# Khoi_Switch.net
KiCad netlist of a schematic drawn in Altium Designer
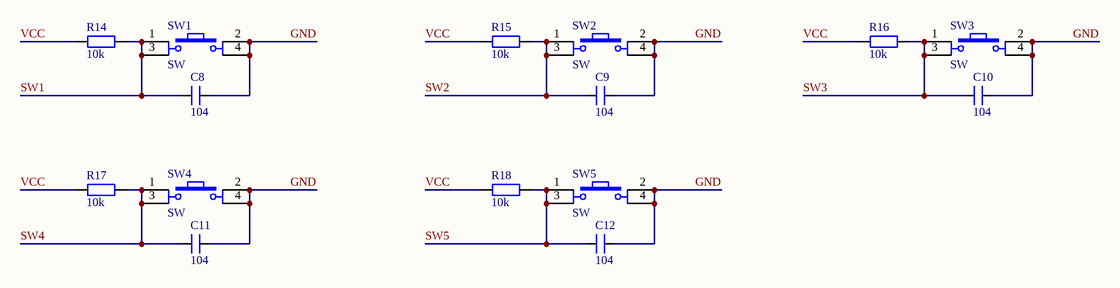
[diagram p0: Khoi_Switch.SchDoc]

(export (version "E")
  (design (tool "Eeschema 10.0.6"))
  (components
    (comp (ref "C8")
      (value "104")
      (footprint "CN2")
      (description "Cap np 104 => 105pF")
      (libsource (lib "My Library") (part "CN2"))
    )
    (comp (ref "C9")
      (value "104")
      (footprint "CN2")
      (description "Cap np 104 => 105pF")
      (libsource (lib "My Library") (part "CN2"))
    )
    (comp (ref "C10")
      (value "104")
      (footprint "CN2")
      (description "Cap np 104 => 105pF")
      (libsource (lib "My Library") (part "CN2"))
    )
    (comp (ref "C11")
      (value "104")
      (footprint "CN2")
      (description "Cap np 104 => 105pF")
      (libsource (lib "My Library") (part "CN2"))
    )
    (comp (ref "C12")
      (value "104")
      (footprint "CN2")
      (description "Cap np 104 => 105pF")
      (libsource (lib "My Library") (part "CN2"))
    )
    (comp (ref "R14")
      (value "10k")
      (footprint "R1/4W")
      (description "Resistor 1/4W")
      (libsource (lib "My Library") (part "R1/4W"))
    )
    (comp (ref "R15")
      (value "10k")
      (footprint "R1/4W")
      (description "Resistor 1/4W")
      (libsource (lib "My Library") (part "R1/4W"))
    )
    (comp (ref "R16")
      (value "10k")
      (footprint "R1/4W")
      (description "Resistor 1/4W")
      (libsource (lib "My Library") (part "R1/4W"))
    )
    (comp (ref "R17")
      (value "10k")
      (footprint "R1/4W")
      (description "Resistor 1/4W")
      (libsource (lib "My Library") (part "R1/4W"))
    )
    (comp (ref "R18")
      (value "10k")
      (footprint "R1/4W")
      (description "Resistor 1/4W")
      (libsource (lib "My Library") (part "R1/4W"))
    )
    (comp (ref "SW1")
      (value "SW")
      (footprint "SW4")
      (description "Switch button 4 pin")
      (libsource (lib "My Library") (part "SW4"))
    )
    (comp (ref "SW2")
      (value "SW")
      (footprint "SW4")
      (description "Switch button 4 pin")
      (libsource (lib "My Library") (part "SW4"))
    )
    (comp (ref "SW3")
      (value "SW")
      (footprint "SW4")
      (description "Switch button 4 pin")
      (libsource (lib "My Library") (part "SW4"))
    )
    (comp (ref "SW4")
      (value "SW")
      (footprint "SW4")
      (description "Switch button 4 pin")
      (libsource (lib "My Library") (part "SW4"))
    )
    (comp (ref "SW5")
      (value "SW")
      (footprint "SW4")
      (description "Switch button 4 pin")
      (libsource (lib "My Library") (part "SW4"))
    )
  )
  (nets
    (net (code "1") (name "/GND") (class "Default")
      (node (ref "C10") (pin "2") (pinfunction "2_2") (pintype "passive"))
      (node (ref "C11") (pin "2") (pinfunction "2_2") (pintype "passive"))
      (node (ref "C12") (pin "2") (pinfunction "2_2") (pintype "passive"))
      (node (ref "C8") (pin "2") (pinfunction "2_2") (pintype "passive"))
      (node (ref "C9") (pin "2") (pinfunction "2_2") (pintype "passive"))
      (node (ref "SW1") (pin "2") (pintype "passive"))
      (node (ref "SW1") (pin "4") (pintype "passive"))
      (node (ref "SW2") (pin "2") (pintype "passive"))
      (node (ref "SW2") (pin "4") (pintype "passive"))
      (node (ref "SW3") (pin "2") (pintype "passive"))
      (node (ref "SW3") (pin "4") (pintype "passive"))
      (node (ref "SW4") (pin "2") (pintype "passive"))
      (node (ref "SW4") (pin "4") (pintype "passive"))
      (node (ref "SW5") (pin "2") (pintype "passive"))
      (node (ref "SW5") (pin "4") (pintype "passive"))
    )
    (net (code "2") (name "/SW1") (class "Default")
      (node (ref "C8") (pin "1") (pinfunction "1_1") (pintype "passive"))
      (node (ref "R14") (pin "2") (pinfunction "2_2") (pintype "passive"))
      (node (ref "SW1") (pin "1") (pintype "passive"))
      (node (ref "SW1") (pin "3") (pintype "passive"))
    )
    (net (code "3") (name "/SW2") (class "Default")
      (node (ref "C9") (pin "1") (pinfunction "1_1") (pintype "passive"))
      (node (ref "R15") (pin "2") (pinfunction "2_2") (pintype "passive"))
      (node (ref "SW2") (pin "1") (pintype "passive"))
      (node (ref "SW2") (pin "3") (pintype "passive"))
    )
    (net (code "4") (name "/SW3") (class "Default")
      (node (ref "C10") (pin "1") (pinfunction "1_1") (pintype "passive"))
      (node (ref "R16") (pin "2") (pinfunction "2_2") (pintype "passive"))
      (node (ref "SW3") (pin "1") (pintype "passive"))
      (node (ref "SW3") (pin "3") (pintype "passive"))
    )
    (net (code "5") (name "/SW4") (class "Default")
      (node (ref "C11") (pin "1") (pinfunction "1_1") (pintype "passive"))
      (node (ref "R17") (pin "2") (pinfunction "2_2") (pintype "passive"))
      (node (ref "SW4") (pin "1") (pintype "passive"))
      (node (ref "SW4") (pin "3") (pintype "passive"))
    )
    (net (code "6") (name "/SW5") (class "Default")
      (node (ref "C12") (pin "1") (pinfunction "1_1") (pintype "passive"))
      (node (ref "R18") (pin "2") (pinfunction "2_2") (pintype "passive"))
      (node (ref "SW5") (pin "1") (pintype "passive"))
      (node (ref "SW5") (pin "3") (pintype "passive"))
    )
    (net (code "7") (name "/VCC") (class "Default")
      (node (ref "R14") (pin "1") (pinfunction "1_1") (pintype "passive"))
      (node (ref "R15") (pin "1") (pinfunction "1_1") (pintype "passive"))
      (node (ref "R16") (pin "1") (pinfunction "1_1") (pintype "passive"))
      (node (ref "R17") (pin "1") (pinfunction "1_1") (pintype "passive"))
      (node (ref "R18") (pin "1") (pinfunction "1_1") (pintype "passive"))
    )
  )
)
